# Zio_Qwiic_Mux.net
KiCad netlist of a schematic drawn in EAGLE
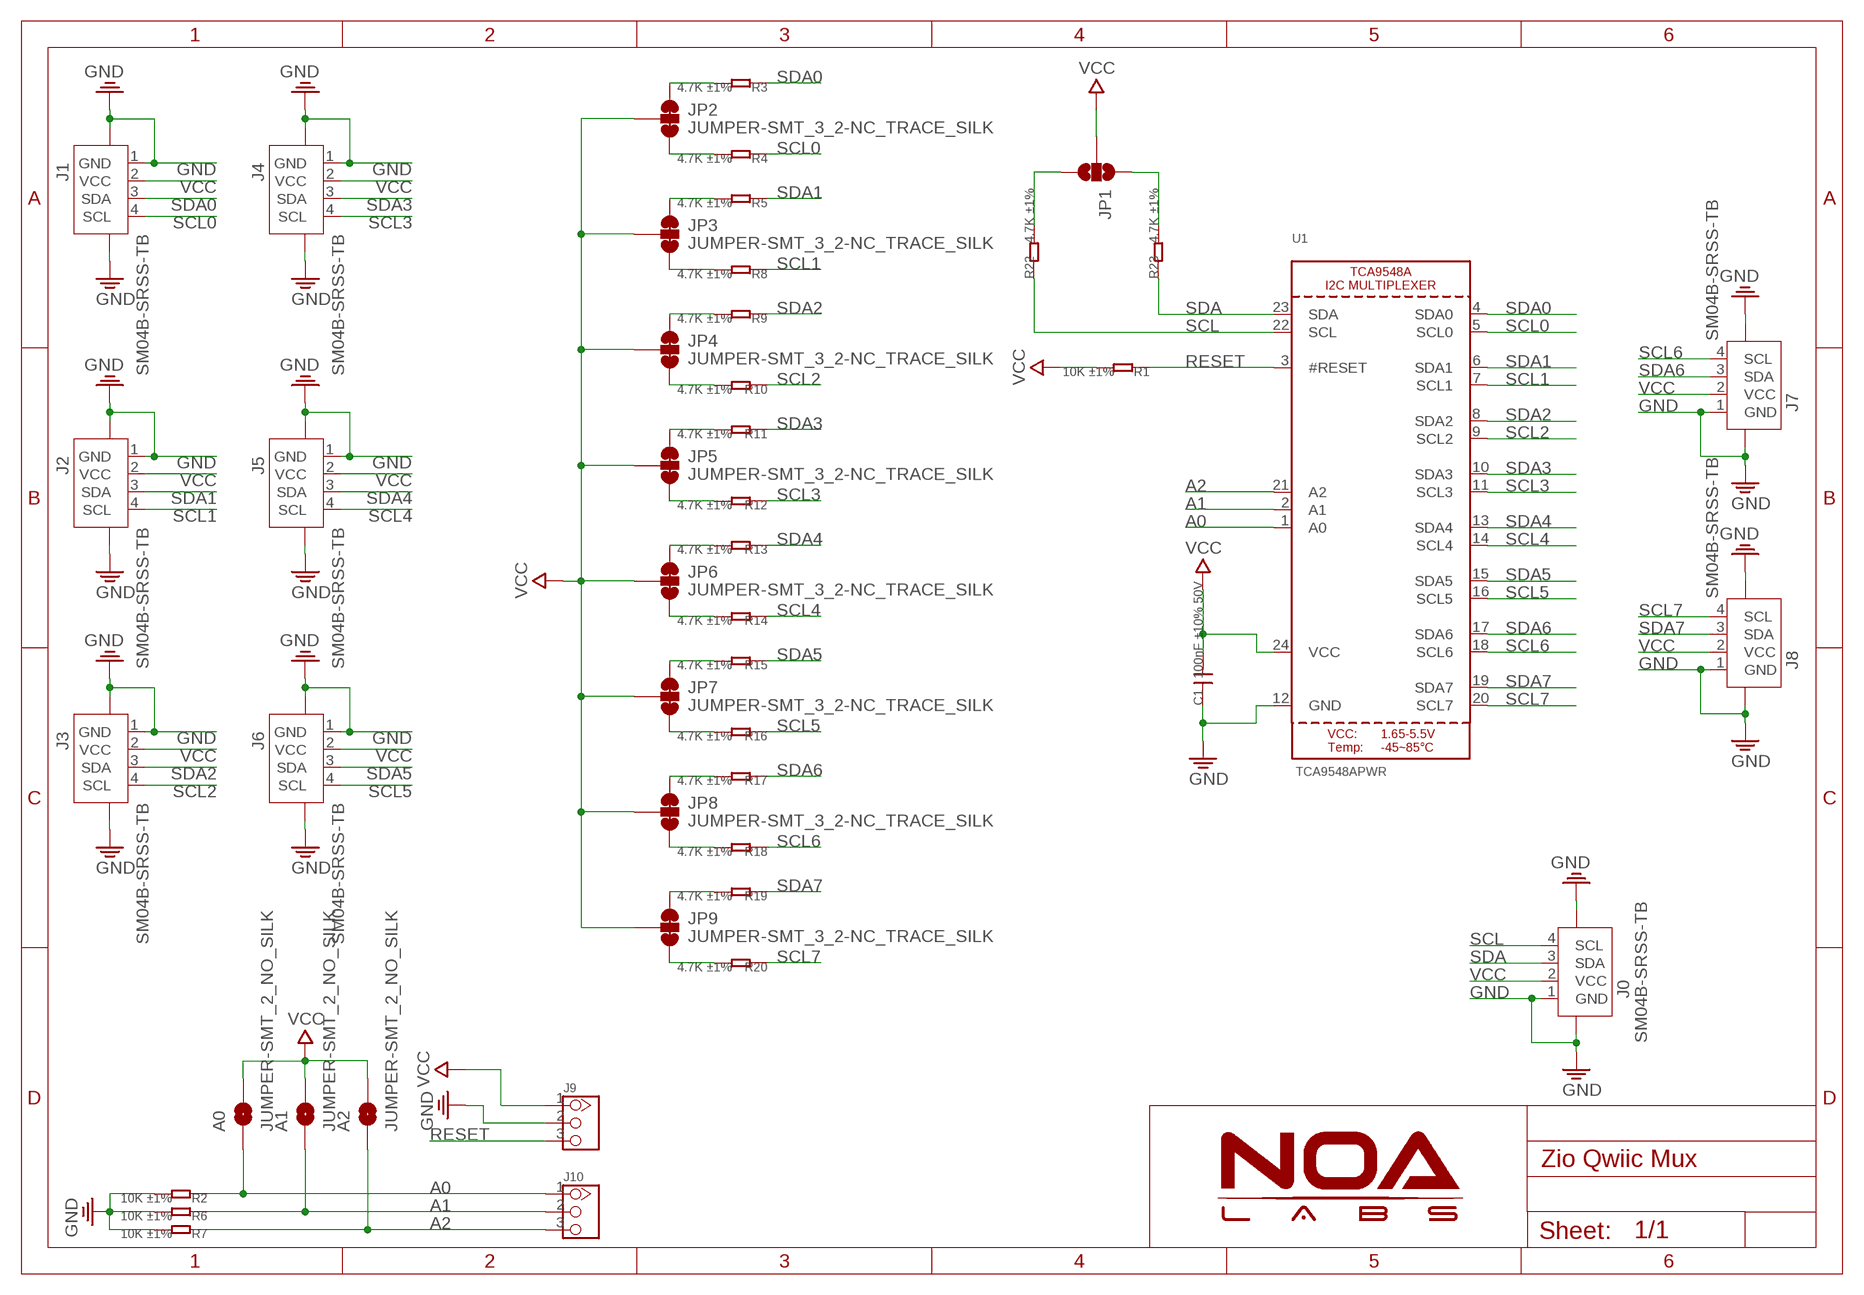
[diagram p0: schematic, sheet 1]

(export (version "E")
  (design (tool "Eeschema 10.0.6"))
  (components
    (comp (ref "A0")
      (value "JUMPER-SMT_2_NO_SILK")
      (footprint "eagle-import:SMT-JUMPER_2_NO_SILK")
      (libsource (lib "eagle-import") (part "JUMPER-SMT_2_NO_SILK"))
    )
    (comp (ref "A1")
      (value "JUMPER-SMT_2_NO_SILK")
      (footprint "eagle-import:SMT-JUMPER_2_NO_SILK")
      (libsource (lib "eagle-import") (part "JUMPER-SMT_2_NO_SILK"))
    )
    (comp (ref "A2")
      (value "JUMPER-SMT_2_NO_SILK")
      (footprint "eagle-import:SMT-JUMPER_2_NO_SILK")
      (libsource (lib "eagle-import") (part "JUMPER-SMT_2_NO_SILK"))
    )
    (comp (ref "C1")
      (value "100nF ±10% 50V")
      (footprint "eagle-import:0603")
      (libsource (lib "eagle-import") (part "C-0603"))
    )
    (comp (ref "J0")
      (value "SM04B-SRSS-TB")
      (footprint "eagle-import:JST-SH-4P")
      (libsource (lib "eagle-import") (part "JST-SH-4P-1.0"))
    )
    (comp (ref "J1")
      (value "SM04B-SRSS-TB")
      (footprint "eagle-import:JST-SH-4P")
      (libsource (lib "eagle-import") (part "JST-SH-4P-1.0"))
    )
    (comp (ref "J2")
      (value "SM04B-SRSS-TB")
      (footprint "eagle-import:JST-SH-4P")
      (libsource (lib "eagle-import") (part "JST-SH-4P-1.0"))
    )
    (comp (ref "J3")
      (value "SM04B-SRSS-TB")
      (footprint "eagle-import:JST-SH-4P")
      (libsource (lib "eagle-import") (part "JST-SH-4P-1.0"))
    )
    (comp (ref "J4")
      (value "SM04B-SRSS-TB")
      (footprint "eagle-import:JST-SH-4P")
      (libsource (lib "eagle-import") (part "JST-SH-4P-1.0"))
    )
    (comp (ref "J5")
      (value "SM04B-SRSS-TB")
      (footprint "eagle-import:JST-SH-4P")
      (libsource (lib "eagle-import") (part "JST-SH-4P-1.0"))
    )
    (comp (ref "J6")
      (value "SM04B-SRSS-TB")
      (footprint "eagle-import:JST-SH-4P")
      (libsource (lib "eagle-import") (part "JST-SH-4P-1.0"))
    )
    (comp (ref "J7")
      (value "SM04B-SRSS-TB")
      (footprint "eagle-import:JST-SH-4P")
      (libsource (lib "eagle-import") (part "JST-SH-4P-1.0"))
    )
    (comp (ref "J8")
      (value "SM04B-SRSS-TB")
      (footprint "eagle-import:JST-SH-4P")
      (libsource (lib "eagle-import") (part "JST-SH-4P-1.0"))
    )
    (comp (ref "J9")
      (value "HEADER-3P-2.54")
      (footprint "eagle-import:3P-2.54")
      (libsource (lib "eagle-import") (part "HEADER-3P-2.54"))
    )
    (comp (ref "J10")
      (value "HEADER-3P-2.54")
      (footprint "eagle-import:3P-2.54")
      (libsource (lib "eagle-import") (part "HEADER-3P-2.54"))
    )
    (comp (ref "JP1")
      (value "JUMPER-SMT_3_2-NC_PASTE_NOCREM")
      (footprint "eagle-import:SMT-JUMPER_3_2-NC_PASTE_SILK_NOCREM")
      (libsource (lib "eagle-import") (part "JUMPER-SMT_3_2-NC_PASTE_NOCREM"))
    )
    (comp (ref "JP2")
      (value "JUMPER-SMT_3_2-NC_TRACE_SILK")
      (footprint "eagle-import:SMT-JUMPER_3_2-NC_TRACE_SILK")
      (libsource (lib "eagle-import") (part "JUMPER-SMT_3_2-NC_TRACE_SILK"))
    )
    (comp (ref "JP3")
      (value "JUMPER-SMT_3_2-NC_TRACE_SILK")
      (footprint "eagle-import:SMT-JUMPER_3_2-NC_TRACE_SILK")
      (libsource (lib "eagle-import") (part "JUMPER-SMT_3_2-NC_TRACE_SILK"))
    )
    (comp (ref "JP4")
      (value "JUMPER-SMT_3_2-NC_TRACE_SILK")
      (footprint "eagle-import:SMT-JUMPER_3_2-NC_TRACE_SILK")
      (libsource (lib "eagle-import") (part "JUMPER-SMT_3_2-NC_TRACE_SILK"))
    )
    (comp (ref "JP5")
      (value "JUMPER-SMT_3_2-NC_TRACE_SILK")
      (footprint "eagle-import:SMT-JUMPER_3_2-NC_TRACE_SILK")
      (libsource (lib "eagle-import") (part "JUMPER-SMT_3_2-NC_TRACE_SILK"))
    )
    (comp (ref "JP6")
      (value "JUMPER-SMT_3_2-NC_TRACE_SILK")
      (footprint "eagle-import:SMT-JUMPER_3_2-NC_TRACE_SILK")
      (libsource (lib "eagle-import") (part "JUMPER-SMT_3_2-NC_TRACE_SILK"))
    )
    (comp (ref "JP7")
      (value "JUMPER-SMT_3_2-NC_TRACE_SILK")
      (footprint "eagle-import:SMT-JUMPER_3_2-NC_TRACE_SILK")
      (libsource (lib "eagle-import") (part "JUMPER-SMT_3_2-NC_TRACE_SILK"))
    )
    (comp (ref "JP8")
      (value "JUMPER-SMT_3_2-NC_TRACE_SILK")
      (footprint "eagle-import:SMT-JUMPER_3_2-NC_TRACE_SILK")
      (libsource (lib "eagle-import") (part "JUMPER-SMT_3_2-NC_TRACE_SILK"))
    )
    (comp (ref "JP9")
      (value "JUMPER-SMT_3_2-NC_TRACE_SILK")
      (footprint "eagle-import:SMT-JUMPER_3_2-NC_TRACE_SILK")
      (libsource (lib "eagle-import") (part "JUMPER-SMT_3_2-NC_TRACE_SILK"))
    )
    (comp (ref "R1")
      (value "10K ±1%")
      (footprint "eagle-import:0402")
      (libsource (lib "eagle-import") (part "R-0402"))
    )
    (comp (ref "R2")
      (value "10K ±1%")
      (footprint "eagle-import:0402")
      (libsource (lib "eagle-import") (part "R-0402"))
    )
    (comp (ref "R3")
      (value "4.7K ±1%")
      (footprint "eagle-import:0402")
      (libsource (lib "eagle-import") (part "R-0402"))
    )
    (comp (ref "R4")
      (value "4.7K ±1%")
      (footprint "eagle-import:0402")
      (libsource (lib "eagle-import") (part "R-0402"))
    )
    (comp (ref "R5")
      (value "4.7K ±1%")
      (footprint "eagle-import:0402")
      (libsource (lib "eagle-import") (part "R-0402"))
    )
    (comp (ref "R6")
      (value "10K ±1%")
      (footprint "eagle-import:0402")
      (libsource (lib "eagle-import") (part "R-0402"))
    )
    (comp (ref "R7")
      (value "10K ±1%")
      (footprint "eagle-import:0402")
      (libsource (lib "eagle-import") (part "R-0402"))
    )
    (comp (ref "R8")
      (value "4.7K ±1%")
      (footprint "eagle-import:0402")
      (libsource (lib "eagle-import") (part "R-0402"))
    )
    (comp (ref "R9")
      (value "4.7K ±1%")
      (footprint "eagle-import:0402")
      (libsource (lib "eagle-import") (part "R-0402"))
    )
    (comp (ref "R10")
      (value "4.7K ±1%")
      (footprint "eagle-import:0402")
      (libsource (lib "eagle-import") (part "R-0402"))
    )
    (comp (ref "R11")
      (value "4.7K ±1%")
      (footprint "eagle-import:0402")
      (libsource (lib "eagle-import") (part "R-0402"))
    )
    (comp (ref "R12")
      (value "4.7K ±1%")
      (footprint "eagle-import:0402")
      (libsource (lib "eagle-import") (part "R-0402"))
    )
    (comp (ref "R13")
      (value "4.7K ±1%")
      (footprint "eagle-import:0402")
      (libsource (lib "eagle-import") (part "R-0402"))
    )
    (comp (ref "R14")
      (value "4.7K ±1%")
      (footprint "eagle-import:0402")
      (libsource (lib "eagle-import") (part "R-0402"))
    )
    (comp (ref "R15")
      (value "4.7K ±1%")
      (footprint "eagle-import:0402")
      (libsource (lib "eagle-import") (part "R-0402"))
    )
    (comp (ref "R16")
      (value "4.7K ±1%")
      (footprint "eagle-import:0402")
      (libsource (lib "eagle-import") (part "R-0402"))
    )
    (comp (ref "R17")
      (value "4.7K ±1%")
      (footprint "eagle-import:0402")
      (libsource (lib "eagle-import") (part "R-0402"))
    )
    (comp (ref "R18")
      (value "4.7K ±1%")
      (footprint "eagle-import:0402")
      (libsource (lib "eagle-import") (part "R-0402"))
    )
    (comp (ref "R19")
      (value "4.7K ±1%")
      (footprint "eagle-import:0402")
      (libsource (lib "eagle-import") (part "R-0402"))
    )
    (comp (ref "R20")
      (value "4.7K ±1%")
      (footprint "eagle-import:0402")
      (libsource (lib "eagle-import") (part "R-0402"))
    )
    (comp (ref "R22")
      (value "4.7K ±1%")
      (footprint "eagle-import:0402")
      (libsource (lib "eagle-import") (part "R-0402"))
    )
    (comp (ref "R23")
      (value "4.7K ±1%")
      (footprint "eagle-import:0402")
      (libsource (lib "eagle-import") (part "R-0402"))
    )
    (comp (ref "U1")
      (value "TCA9548APWR")
      (footprint "eagle-import:TSSOP24")
      (libsource (lib "eagle-import") (part "TCA9548A"))
    )
  )
  (nets
    (net (code "1") (name "/A0") (class "Default")
      (node (ref "A0") (pin "1") (pinfunction "1_1") (pintype "passive"))
      (node (ref "J10") (pin "1") (pinfunction "P$1_1") (pintype "bidirectional"))
      (node (ref "R2") (pin "1") (pinfunction "1_1") (pintype "passive"))
      (node (ref "U1") (pin "1") (pinfunction "A0_1") (pintype "bidirectional"))
    )
    (net (code "2") (name "/A1") (class "Default")
      (node (ref "A1") (pin "1") (pinfunction "1_1") (pintype "passive"))
      (node (ref "J10") (pin "2") (pinfunction "P$2_2") (pintype "bidirectional"))
      (node (ref "R6") (pin "1") (pinfunction "1_1") (pintype "passive"))
      (node (ref "U1") (pin "2") (pinfunction "A1_2") (pintype "bidirectional"))
    )
    (net (code "3") (name "/A2") (class "Default")
      (node (ref "A2") (pin "1") (pinfunction "1_1") (pintype "passive"))
      (node (ref "J10") (pin "3") (pinfunction "P$3_3") (pintype "bidirectional"))
      (node (ref "R7") (pin "1") (pinfunction "1_1") (pintype "passive"))
      (node (ref "U1") (pin "21") (pinfunction "A2_21") (pintype "bidirectional"))
    )
    (net (code "4") (name "/RESET") (class "Default")
      (node (ref "J9") (pin "3") (pinfunction "P$3_3") (pintype "bidirectional"))
      (node (ref "R1") (pin "1") (pinfunction "1_1") (pintype "passive"))
      (node (ref "U1") (pin "3") (pinfunction "#RESET_3") (pintype "bidirectional"))
    )
    (net (code "5") (name "/SCL") (class "Default")
      (node (ref "J0") (pin "4") (pinfunction "SCL_4") (pintype "bidirectional"))
      (node (ref "R22") (pin "1") (pinfunction "1_1") (pintype "passive"))
      (node (ref "U1") (pin "22") (pinfunction "SCL_22") (pintype "bidirectional"))
    )
    (net (code "6") (name "/SCL0") (class "Default")
      (node (ref "J1") (pin "4") (pinfunction "SCL_4") (pintype "bidirectional"))
      (node (ref "R4") (pin "1") (pinfunction "1_1") (pintype "passive"))
      (node (ref "U1") (pin "5") (pinfunction "SCL0_5") (pintype "bidirectional"))
    )
    (net (code "7") (name "/SCL1") (class "Default")
      (node (ref "J2") (pin "4") (pinfunction "SCL_4") (pintype "bidirectional"))
      (node (ref "R8") (pin "1") (pinfunction "1_1") (pintype "passive"))
      (node (ref "U1") (pin "7") (pinfunction "SCL1_7") (pintype "bidirectional"))
    )
    (net (code "8") (name "/SCL2") (class "Default")
      (node (ref "J3") (pin "4") (pinfunction "SCL_4") (pintype "bidirectional"))
      (node (ref "R10") (pin "1") (pinfunction "1_1") (pintype "passive"))
      (node (ref "U1") (pin "9") (pinfunction "SCL2_9") (pintype "bidirectional"))
    )
    (net (code "9") (name "/SCL3") (class "Default")
      (node (ref "J4") (pin "4") (pinfunction "SCL_4") (pintype "bidirectional"))
      (node (ref "R12") (pin "1") (pinfunction "1_1") (pintype "passive"))
      (node (ref "U1") (pin "11") (pinfunction "SCL3_11") (pintype "bidirectional"))
    )
    (net (code "10") (name "/SCL4") (class "Default")
      (node (ref "J5") (pin "4") (pinfunction "SCL_4") (pintype "bidirectional"))
      (node (ref "R14") (pin "1") (pinfunction "1_1") (pintype "passive"))
      (node (ref "U1") (pin "14") (pinfunction "SCL4_14") (pintype "bidirectional"))
    )
    (net (code "11") (name "/SCL5") (class "Default")
      (node (ref "J6") (pin "4") (pinfunction "SCL_4") (pintype "bidirectional"))
      (node (ref "R16") (pin "1") (pinfunction "1_1") (pintype "passive"))
      (node (ref "U1") (pin "16") (pinfunction "SCL5_16") (pintype "bidirectional"))
    )
    (net (code "12") (name "/SCL6") (class "Default")
      (node (ref "J7") (pin "4") (pinfunction "SCL_4") (pintype "bidirectional"))
      (node (ref "R18") (pin "1") (pinfunction "1_1") (pintype "passive"))
      (node (ref "U1") (pin "18") (pinfunction "SCL6_18") (pintype "bidirectional"))
    )
    (net (code "13") (name "/SCL7") (class "Default")
      (node (ref "J8") (pin "4") (pinfunction "SCL_4") (pintype "bidirectional"))
      (node (ref "R20") (pin "1") (pinfunction "1_1") (pintype "passive"))
      (node (ref "U1") (pin "20") (pinfunction "SCL7_20") (pintype "bidirectional"))
    )
    (net (code "14") (name "/SDA") (class "Default")
      (node (ref "J0") (pin "3") (pinfunction "SDA_3") (pintype "bidirectional"))
      (node (ref "R23") (pin "1") (pinfunction "1_1") (pintype "passive"))
      (node (ref "U1") (pin "23") (pinfunction "SDA_23") (pintype "bidirectional"))
    )
    (net (code "15") (name "/SDA0") (class "Default")
      (node (ref "J1") (pin "3") (pinfunction "SDA_3") (pintype "bidirectional"))
      (node (ref "R3") (pin "1") (pinfunction "1_1") (pintype "passive"))
      (node (ref "U1") (pin "4") (pinfunction "SDA0_4") (pintype "bidirectional"))
    )
    (net (code "16") (name "/SDA1") (class "Default")
      (node (ref "J2") (pin "3") (pinfunction "SDA_3") (pintype "bidirectional"))
      (node (ref "R5") (pin "1") (pinfunction "1_1") (pintype "passive"))
      (node (ref "U1") (pin "6") (pinfunction "SDA1_6") (pintype "bidirectional"))
    )
    (net (code "17") (name "/SDA2") (class "Default")
      (node (ref "J3") (pin "3") (pinfunction "SDA_3") (pintype "bidirectional"))
      (node (ref "R9") (pin "1") (pinfunction "1_1") (pintype "passive"))
      (node (ref "U1") (pin "8") (pinfunction "SDA2_8") (pintype "bidirectional"))
    )
    (net (code "18") (name "/SDA3") (class "Default")
      (node (ref "J4") (pin "3") (pinfunction "SDA_3") (pintype "bidirectional"))
      (node (ref "R11") (pin "1") (pinfunction "1_1") (pintype "passive"))
      (node (ref "U1") (pin "10") (pinfunction "SDA3_10") (pintype "bidirectional"))
    )
    (net (code "19") (name "/SDA4") (class "Default")
      (node (ref "J5") (pin "3") (pinfunction "SDA_3") (pintype "bidirectional"))
      (node (ref "R13") (pin "1") (pinfunction "1_1") (pintype "passive"))
      (node (ref "U1") (pin "13") (pinfunction "SDA4_13") (pintype "bidirectional"))
    )
    (net (code "20") (name "/SDA5") (class "Default")
      (node (ref "J6") (pin "3") (pinfunction "SDA_3") (pintype "bidirectional"))
      (node (ref "R15") (pin "1") (pinfunction "1_1") (pintype "passive"))
      (node (ref "U1") (pin "15") (pinfunction "SDA5_15") (pintype "bidirectional"))
    )
    (net (code "21") (name "/SDA6") (class "Default")
      (node (ref "J7") (pin "3") (pinfunction "SDA_3") (pintype "bidirectional"))
      (node (ref "R17") (pin "1") (pinfunction "1_1") (pintype "passive"))
      (node (ref "U1") (pin "17") (pinfunction "SDA6_17") (pintype "bidirectional"))
    )
    (net (code "22") (name "/SDA7") (class "Default")
      (node (ref "J8") (pin "3") (pinfunction "SDA_3") (pintype "bidirectional"))
      (node (ref "R19") (pin "1") (pinfunction "1_1") (pintype "passive"))
      (node (ref "U1") (pin "19") (pinfunction "SDA7_19") (pintype "bidirectional"))
    )
    (net (code "23") (name "GND") (class "Default")
      (node (ref "C1") (pin "1") (pinfunction "1_1") (pintype "passive"))
      (node (ref "J0") (pin "1") (pinfunction "GND_1") (pintype "bidirectional"))
      (node (ref "J0") (pin "NC1") (pinfunction "5_NC1") (pintype "bidirectional"))
      (node (ref "J0") (pin "NC2") (pinfunction "6_NC2") (pintype "bidirectional"))
      (node (ref "J1") (pin "1") (pinfunction "GND_1") (pintype "bidirectional"))
      (node (ref "J1") (pin "NC1") (pinfunction "5_NC1") (pintype "bidirectional"))
      (node (ref "J1") (pin "NC2") (pinfunction "6_NC2") (pintype "bidirectional"))
      (node (ref "J2") (pin "1") (pinfunction "GND_1") (pintype "bidirectional"))
      (node (ref "J2") (pin "NC1") (pinfunction "5_NC1") (pintype "bidirectional"))
      (node (ref "J2") (pin "NC2") (pinfunction "6_NC2") (pintype "bidirectional"))
      (node (ref "J3") (pin "1") (pinfunction "GND_1") (pintype "bidirectional"))
      (node (ref "J3") (pin "NC1") (pinfunction "5_NC1") (pintype "bidirectional"))
      (node (ref "J3") (pin "NC2") (pinfunction "6_NC2") (pintype "bidirectional"))
      (node (ref "J4") (pin "1") (pinfunction "GND_1") (pintype "bidirectional"))
      (node (ref "J4") (pin "NC1") (pinfunction "5_NC1") (pintype "bidirectional"))
      (node (ref "J4") (pin "NC2") (pinfunction "6_NC2") (pintype "bidirectional"))
      (node (ref "J5") (pin "1") (pinfunction "GND_1") (pintype "bidirectional"))
      (node (ref "J5") (pin "NC1") (pinfunction "5_NC1") (pintype "bidirectional"))
      (node (ref "J5") (pin "NC2") (pinfunction "6_NC2") (pintype "bidirectional"))
      (node (ref "J6") (pin "1") (pinfunction "GND_1") (pintype "bidirectional"))
      (node (ref "J6") (pin "NC1") (pinfunction "5_NC1") (pintype "bidirectional"))
      (node (ref "J6") (pin "NC2") (pinfunction "6_NC2") (pintype "bidirectional"))
      (node (ref "J7") (pin "1") (pinfunction "GND_1") (pintype "bidirectional"))
      (node (ref "J7") (pin "NC1") (pinfunction "5_NC1") (pintype "bidirectional"))
      (node (ref "J7") (pin "NC2") (pinfunction "6_NC2") (pintype "bidirectional"))
      (node (ref "J8") (pin "1") (pinfunction "GND_1") (pintype "bidirectional"))
      (node (ref "J8") (pin "NC1") (pinfunction "5_NC1") (pintype "bidirectional"))
      (node (ref "J8") (pin "NC2") (pinfunction "6_NC2") (pintype "bidirectional"))
      (node (ref "J9") (pin "2") (pinfunction "P$2_2") (pintype "bidirectional"))
      (node (ref "R2") (pin "2") (pinfunction "2_2") (pintype "passive"))
      (node (ref "R6") (pin "2") (pinfunction "2_2") (pintype "passive"))
      (node (ref "R7") (pin "2") (pinfunction "2_2") (pintype "passive"))
      (node (ref "U1") (pin "12") (pinfunction "GND_12") (pintype "bidirectional"))
    )
    (net (code "24") (name "Net-(JP1-Pad1)") (class "Default")
      (node (ref "JP1") (pin "1") (pinfunction "1_1") (pintype "passive"))
      (node (ref "R23") (pin "2") (pinfunction "2_2") (pintype "passive"))
    )
    (net (code "25") (name "Net-(JP1-Pad3)") (class "Default")
      (node (ref "JP1") (pin "3") (pinfunction "3_3") (pintype "passive"))
      (node (ref "R22") (pin "2") (pinfunction "2_2") (pintype "passive"))
    )
    (net (code "26") (name "Net-(JP2-Pad1)") (class "Default")
      (node (ref "JP2") (pin "1") (pinfunction "1_1") (pintype "passive"))
      (node (ref "R3") (pin "2") (pinfunction "2_2") (pintype "passive"))
    )
    (net (code "27") (name "Net-(JP2-Pad3)") (class "Default")
      (node (ref "JP2") (pin "3") (pinfunction "3_3") (pintype "passive"))
      (node (ref "R4") (pin "2") (pinfunction "2_2") (pintype "passive"))
    )
    (net (code "28") (name "Net-(JP3-Pad1)") (class "Default")
      (node (ref "JP3") (pin "1") (pinfunction "1_1") (pintype "passive"))
      (node (ref "R5") (pin "2") (pinfunction "2_2") (pintype "passive"))
    )
    (net (code "29") (name "Net-(JP3-Pad3)") (class "Default")
      (node (ref "JP3") (pin "3") (pinfunction "3_3") (pintype "passive"))
      (node (ref "R8") (pin "2") (pinfunction "2_2") (pintype "passive"))
    )
    (net (code "30") (name "Net-(JP4-Pad1)") (class "Default")
      (node (ref "JP4") (pin "1") (pinfunction "1_1") (pintype "passive"))
      (node (ref "R9") (pin "2") (pinfunction "2_2") (pintype "passive"))
    )
    (net (code "31") (name "Net-(JP4-Pad3)") (class "Default")
      (node (ref "JP4") (pin "3") (pinfunction "3_3") (pintype "passive"))
      (node (ref "R10") (pin "2") (pinfunction "2_2") (pintype "passive"))
    )
    (net (code "32") (name "Net-(JP5-Pad1)") (class "Default")
      (node (ref "JP5") (pin "1") (pinfunction "1_1") (pintype "passive"))
      (node (ref "R11") (pin "2") (pinfunction "2_2") (pintype "passive"))
    )
    (net (code "33") (name "Net-(JP5-Pad3)") (class "Default")
      (node (ref "JP5") (pin "3") (pinfunction "3_3") (pintype "passive"))
      (node (ref "R12") (pin "2") (pinfunction "2_2") (pintype "passive"))
    )
    (net (code "34") (name "Net-(JP6-Pad1)") (class "Default")
      (node (ref "JP6") (pin "1") (pinfunction "1_1") (pintype "passive"))
      (node (ref "R13") (pin "2") (pinfunction "2_2") (pintype "passive"))
    )
    (net (code "35") (name "Net-(JP6-Pad3)") (class "Default")
      (node (ref "JP6") (pin "3") (pinfunction "3_3") (pintype "passive"))
      (node (ref "R14") (pin "2") (pinfunction "2_2") (pintype "passive"))
    )
    (net (code "36") (name "Net-(JP7-Pad1)") (class "Default")
      (node (ref "JP7") (pin "1") (pinfunction "1_1") (pintype "passive"))
      (node (ref "R15") (pin "2") (pinfunction "2_2") (pintype "passive"))
    )
    (net (code "37") (name "Net-(JP7-Pad3)") (class "Default")
      (node (ref "JP7") (pin "3") (pinfunction "3_3") (pintype "passive"))
      (node (ref "R16") (pin "2") (pinfunction "2_2") (pintype "passive"))
    )
    (net (code "38") (name "Net-(JP8-Pad1)") (class "Default")
      (node (ref "JP8") (pin "1") (pinfunction "1_1") (pintype "passive"))
      (node (ref "R17") (pin "2") (pinfunction "2_2") (pintype "passive"))
    )
    (net (code "39") (name "Net-(JP8-Pad3)") (class "Default")
      (node (ref "JP8") (pin "3") (pinfunction "3_3") (pintype "passive"))
      (node (ref "R18") (pin "2") (pinfunction "2_2") (pintype "passive"))
    )
    (net (code "40") (name "Net-(JP9-Pad1)") (class "Default")
      (node (ref "JP9") (pin "1") (pinfunction "1_1") (pintype "passive"))
      (node (ref "R19") (pin "2") (pinfunction "2_2") (pintype "passive"))
    )
    (net (code "41") (name "Net-(JP9-Pad3)") (class "Default")
      (node (ref "JP9") (pin "3") (pinfunction "3_3") (pintype "passive"))
      (node (ref "R20") (pin "2") (pinfunction "2_2") (pintype "passive"))
    )
    (net (code "42") (name "VCC") (class "Default")
      (node (ref "A0") (pin "2") (pinfunction "2_2") (pintype "passive"))
      (node (ref "A1") (pin "2") (pinfunction "2_2") (pintype "passive"))
      (node (ref "A2") (pin "2") (pinfunction "2_2") (pintype "passive"))
      (node (ref "C1") (pin "2") (pinfunction "2_2") (pintype "passive"))
      (node (ref "J0") (pin "2") (pinfunction "VCC_2") (pintype "bidirectional"))
      (node (ref "J1") (pin "2") (pinfunction "VCC_2") (pintype "bidirectional"))
      (node (ref "J2") (pin "2") (pinfunction "VCC_2") (pintype "bidirectional"))
      (node (ref "J3") (pin "2") (pinfunction "VCC_2") (pintype "bidirectional"))
      (node (ref "J4") (pin "2") (pinfunction "VCC_2") (pintype "bidirectional"))
      (node (ref "J5") (pin "2") (pinfunction "VCC_2") (pintype "bidirectional"))
      (node (ref "J6") (pin "2") (pinfunction "VCC_2") (pintype "bidirectional"))
      (node (ref "J7") (pin "2") (pinfunction "VCC_2") (pintype "bidirectional"))
      (node (ref "J8") (pin "2") (pinfunction "VCC_2") (pintype "bidirectional"))
      (node (ref "J9") (pin "1") (pinfunction "P$1_1") (pintype "bidirectional"))
      (node (ref "JP1") (pin "2") (pinfunction "2_2") (pintype "passive"))
      (node (ref "JP2") (pin "2") (pinfunction "2_2") (pintype "passive"))
      (node (ref "JP3") (pin "2") (pinfunction "2_2") (pintype "passive"))
      (node (ref "JP4") (pin "2") (pinfunction "2_2") (pintype "passive"))
      (node (ref "JP5") (pin "2") (pinfunction "2_2") (pintype "passive"))
      (node (ref "JP6") (pin "2") (pinfunction "2_2") (pintype "passive"))
      (node (ref "JP7") (pin "2") (pinfunction "2_2") (pintype "passive"))
      (node (ref "JP8") (pin "2") (pinfunction "2_2") (pintype "passive"))
      (node (ref "JP9") (pin "2") (pinfunction "2_2") (pintype "passive"))
      (node (ref "R1") (pin "2") (pinfunction "2_2") (pintype "passive"))
      (node (ref "U1") (pin "24") (pinfunction "VCC_24") (pintype "bidirectional"))
    )
  )
)
